# ioboard.net
KiCad netlist of a schematic drawn in EAGLE
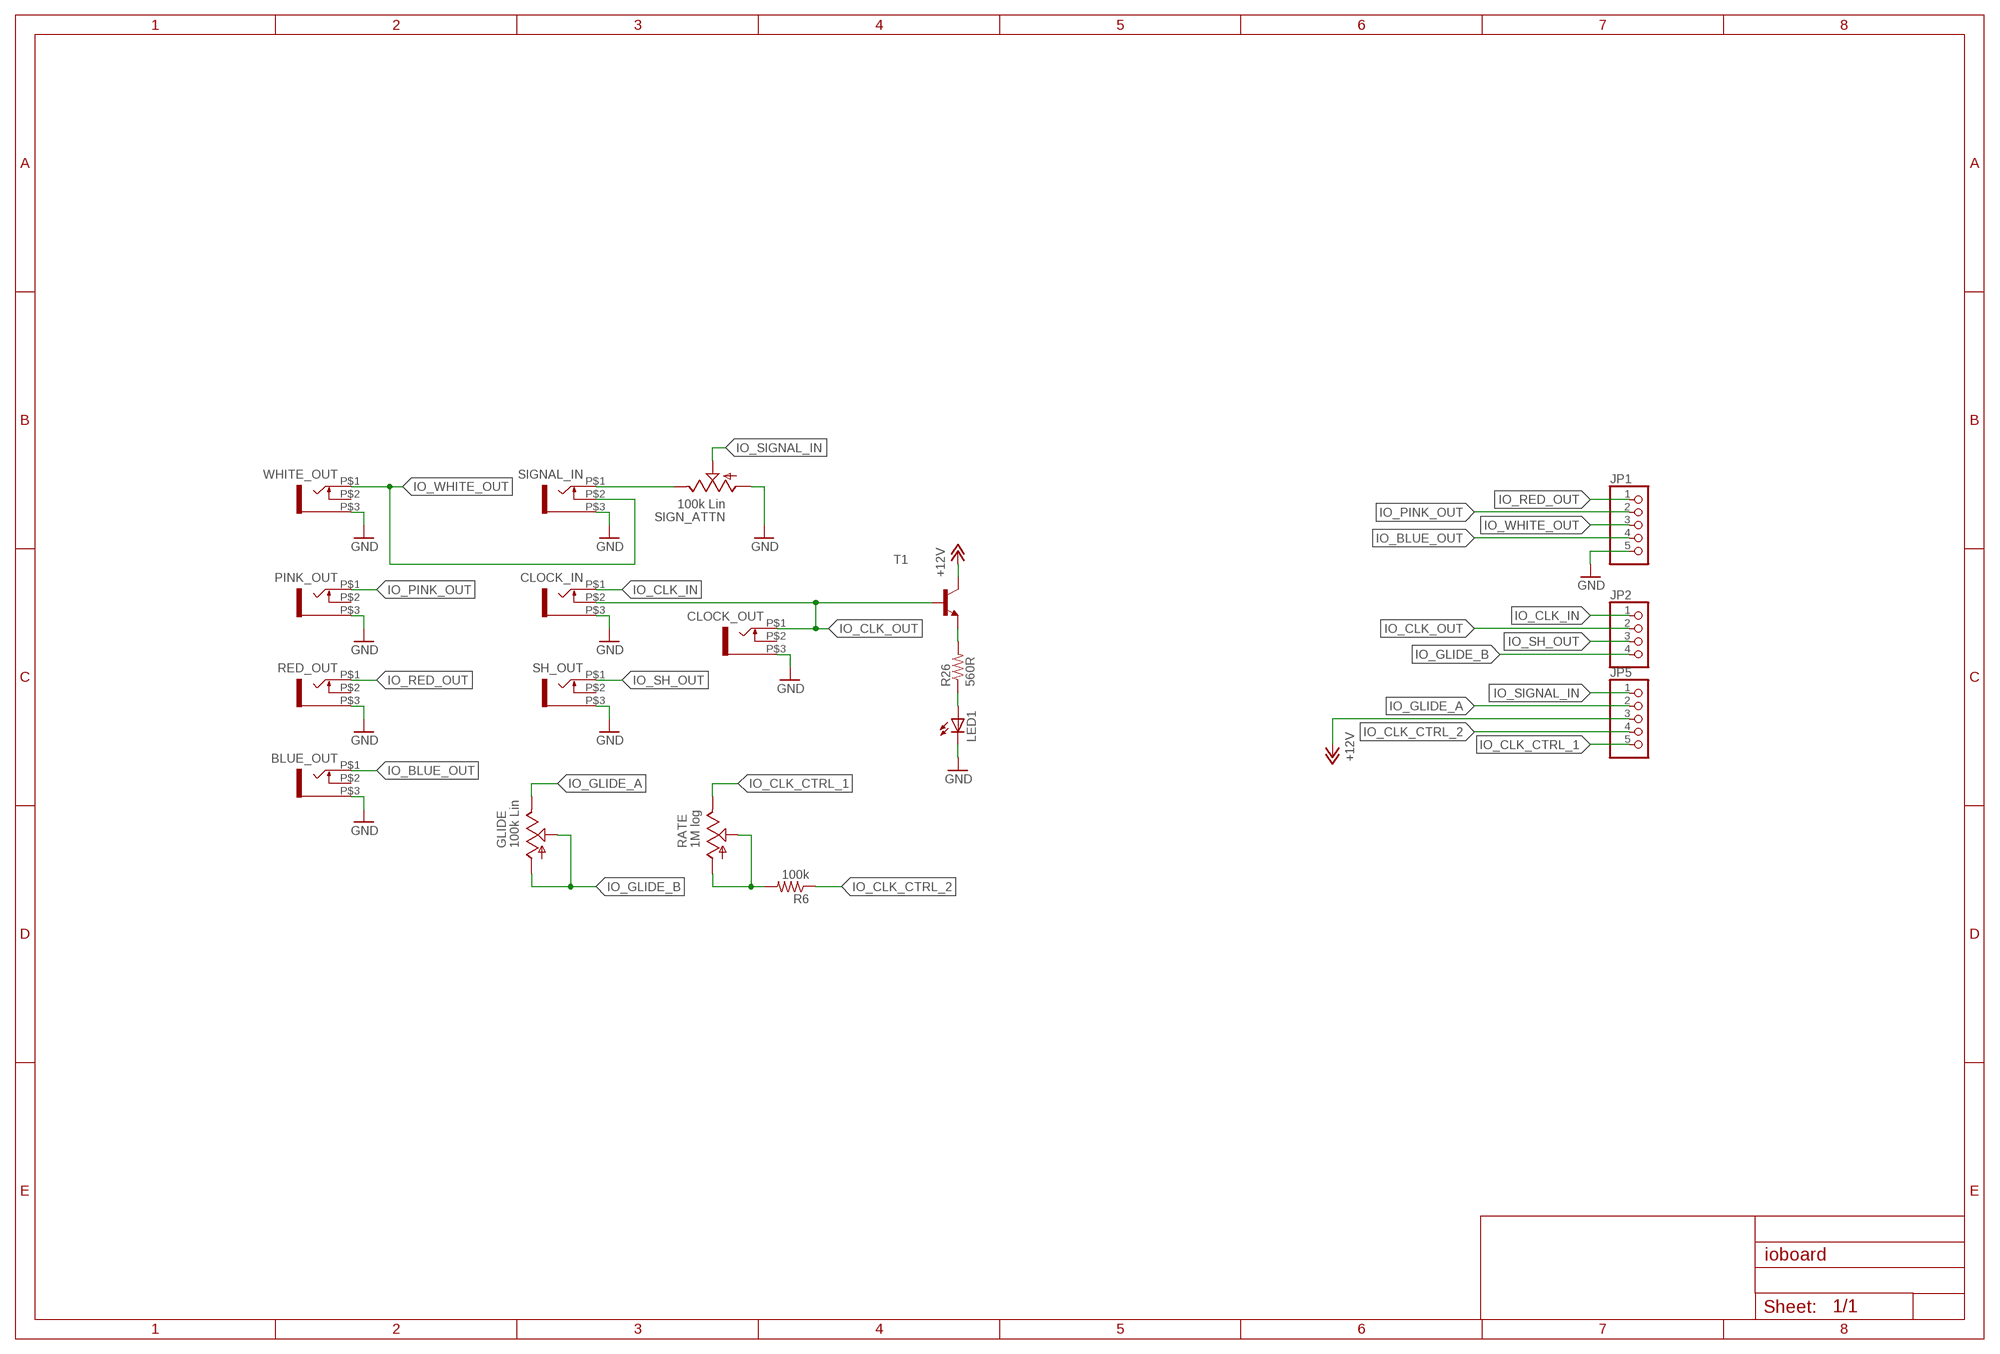
[diagram p0: schematic, sheet 1]

(export (version "E")
  (design (tool "Eeschema 10.0.6"))
  (components
    (comp (ref "BLUE_OUT")
      (value "WQP-PJ301M-12_JACK")
      (footprint "eagle-import:WQP-PJ301M-12_JACK")
      (libsource (lib "eagle-import") (part "WQP-PJ301M-12_JACK"))
    )
    (comp (ref "CLOCK_IN")
      (value "WQP-PJ301M-12_JACK")
      (footprint "eagle-import:WQP-PJ301M-12_JACK")
      (libsource (lib "eagle-import") (part "WQP-PJ301M-12_JACK"))
    )
    (comp (ref "CLOCK_OUT")
      (value "WQP-PJ301M-12_JACK")
      (footprint "eagle-import:WQP-PJ301M-12_JACK")
      (libsource (lib "eagle-import") (part "WQP-PJ301M-12_JACK"))
    )
    (comp (ref "GLIDE")
      (value "100k Lin")
      (footprint "eagle-import:EVUF")
      (libsource (lib "eagle-import") (part "ALPHA-9MMA"))
    )
    (comp (ref "JP1")
      (value "PINHD-1X5")
      (footprint "eagle-import:1X05")
      (libsource (lib "eagle-import") (part "PINHD-1X5"))
    )
    (comp (ref "JP2")
      (value "PINHD-1X4")
      (footprint "eagle-import:1X04")
      (libsource (lib "eagle-import") (part "PINHD-1X4"))
    )
    (comp (ref "JP5")
      (value "PINHD-1X5")
      (footprint "eagle-import:1X05")
      (libsource (lib "eagle-import") (part "PINHD-1X5"))
    )
    (comp (ref "LED1")
      (value "LED3MM")
      (footprint "eagle-import:LED3MM")
      (libsource (lib "eagle-import") (part "LED3MM"))
    )
    (comp (ref "PINK_OUT")
      (value "WQP-PJ301M-12_JACK")
      (footprint "eagle-import:WQP-PJ301M-12_JACK")
      (libsource (lib "eagle-import") (part "WQP-PJ301M-12_JACK"))
    )
    (comp (ref "R6")
      (value "100k")
      (footprint "eagle-import:0204_7")
      (libsource (lib "eagle-import") (part "R-US_0204/7"))
    )
    (comp (ref "R26")
      (value "560R")
      (footprint "eagle-import:0204_7")
      (libsource (lib "eagle-import") (part "R-US_0204/7"))
    )
    (comp (ref "RATE")
      (value "1M log")
      (footprint "eagle-import:EVUF")
      (libsource (lib "eagle-import") (part "ALPHA-9MMA"))
    )
    (comp (ref "RED_OUT")
      (value "WQP-PJ301M-12_JACK")
      (footprint "eagle-import:WQP-PJ301M-12_JACK")
      (libsource (lib "eagle-import") (part "WQP-PJ301M-12_JACK"))
    )
    (comp (ref "SH_OUT")
      (value "WQP-PJ301M-12_JACK")
      (footprint "eagle-import:WQP-PJ301M-12_JACK")
      (libsource (lib "eagle-import") (part "WQP-PJ301M-12_JACK"))
    )
    (comp (ref "SIGNAL_IN")
      (value "WQP-PJ301M-12_JACK")
      (footprint "eagle-import:WQP-PJ301M-12_JACK")
      (libsource (lib "eagle-import") (part "WQP-PJ301M-12_JACK"))
    )
    (comp (ref "SIGN_ATTN")
      (value "100k Lin")
      (footprint "eagle-import:EVUF")
      (libsource (lib "eagle-import") (part "ALPHA-9MMA"))
    )
    (comp (ref "T1")
      (value "BC550-NPN-TO92-CBE")
      (footprint "eagle-import:TO92-CBE")
      (libsource (lib "eagle-import") (part "-NPN-TO92-CBEBC550"))
    )
    (comp (ref "WHITE_OUT")
      (value "WQP-PJ301M-12_JACK")
      (footprint "eagle-import:WQP-PJ301M-12_JACK")
      (libsource (lib "eagle-import") (part "WQP-PJ301M-12_JACK"))
    )
  )
  (nets
    (net (code "1") (name "+12V") (class "Default")
      (node (ref "JP5") (pin "3") (pinfunction "3_3") (pintype "passive"))
      (node (ref "T1") (pin "C") (pinfunction "C_C") (pintype "passive"))
    )
    (net (code "2") (name "GND") (class "Default")
      (node (ref "BLUE_OUT") (pin "P$3") (pinfunction "1_P$3") (pintype "passive"))
      (node (ref "CLOCK_IN") (pin "P$3") (pinfunction "1_P$3") (pintype "passive"))
      (node (ref "CLOCK_OUT") (pin "P$3") (pinfunction "1_P$3") (pintype "passive"))
      (node (ref "JP1") (pin "5") (pinfunction "5_5") (pintype "passive"))
      (node (ref "LED1") (pin "K") (pinfunction "C_K") (pintype "passive"))
      (node (ref "PINK_OUT") (pin "P$3") (pinfunction "1_P$3") (pintype "passive"))
      (node (ref "RED_OUT") (pin "P$3") (pinfunction "1_P$3") (pintype "passive"))
      (node (ref "SH_OUT") (pin "P$3") (pinfunction "1_P$3") (pintype "passive"))
      (node (ref "SIGNAL_IN") (pin "P$3") (pinfunction "1_P$3") (pintype "passive"))
      (node (ref "SIGN_ATTN") (pin "1") (pinfunction "A_1") (pintype "passive"))
      (node (ref "WHITE_OUT") (pin "P$3") (pinfunction "1_P$3") (pintype "passive"))
    )
    (net (code "3") (name "IO_BLUE_OUT") (class "Default")
      (node (ref "BLUE_OUT") (pin "P$1") (pinfunction "2_P$1") (pintype "passive"))
      (node (ref "JP1") (pin "4") (pinfunction "4_4") (pintype "passive"))
    )
    (net (code "4") (name "IO_CLK_CTRL_1") (class "Default")
      (node (ref "JP5") (pin "5") (pinfunction "5_5") (pintype "passive"))
      (node (ref "RATE") (pin "3") (pinfunction "E_3") (pintype "passive"))
    )
    (net (code "5") (name "IO_CLK_CTRL_2") (class "Default")
      (node (ref "JP5") (pin "4") (pinfunction "4_4") (pintype "passive"))
      (node (ref "R6") (pin "1") (pinfunction "1_1") (pintype "passive"))
    )
    (net (code "6") (name "IO_CLK_IN") (class "Default")
      (node (ref "CLOCK_IN") (pin "P$1") (pinfunction "2_P$1") (pintype "passive"))
      (node (ref "JP2") (pin "1") (pinfunction "1_1") (pintype "passive"))
    )
    (net (code "7") (name "IO_CLK_OUT") (class "Default")
      (node (ref "CLOCK_IN") (pin "P$2") (pinfunction "3_P$2") (pintype "passive"))
      (node (ref "CLOCK_OUT") (pin "P$1") (pinfunction "2_P$1") (pintype "passive"))
      (node (ref "JP2") (pin "2") (pinfunction "2_2") (pintype "passive"))
      (node (ref "T1") (pin "B") (pinfunction "B_B") (pintype "passive"))
    )
    (net (code "8") (name "IO_GLIDE_A") (class "Default")
      (node (ref "GLIDE") (pin "3") (pinfunction "E_3") (pintype "passive"))
      (node (ref "JP5") (pin "2") (pinfunction "2_2") (pintype "passive"))
    )
    (net (code "9") (name "IO_GLIDE_B") (class "Default")
      (node (ref "GLIDE") (pin "1") (pinfunction "A_1") (pintype "passive"))
      (node (ref "GLIDE") (pin "2") (pinfunction "S_2") (pintype "passive"))
      (node (ref "JP2") (pin "4") (pinfunction "4_4") (pintype "passive"))
    )
    (net (code "10") (name "IO_PINK_OUT") (class "Default")
      (node (ref "JP1") (pin "2") (pinfunction "2_2") (pintype "passive"))
      (node (ref "PINK_OUT") (pin "P$1") (pinfunction "2_P$1") (pintype "passive"))
    )
    (net (code "11") (name "IO_RED_OUT") (class "Default")
      (node (ref "JP1") (pin "1") (pinfunction "1_1") (pintype "passive"))
      (node (ref "RED_OUT") (pin "P$1") (pinfunction "2_P$1") (pintype "passive"))
    )
    (net (code "12") (name "IO_SH_OUT") (class "Default")
      (node (ref "JP2") (pin "3") (pinfunction "3_3") (pintype "passive"))
      (node (ref "SH_OUT") (pin "P$1") (pinfunction "2_P$1") (pintype "passive"))
    )
    (net (code "13") (name "IO_SIGNAL_IN") (class "Default")
      (node (ref "JP5") (pin "1") (pinfunction "1_1") (pintype "passive"))
      (node (ref "SIGN_ATTN") (pin "2") (pinfunction "S_2") (pintype "passive"))
    )
    (net (code "14") (name "IO_WHITE_OUT") (class "Default")
      (node (ref "JP1") (pin "3") (pinfunction "3_3") (pintype "passive"))
      (node (ref "SIGNAL_IN") (pin "P$2") (pinfunction "3_P$2") (pintype "passive"))
      (node (ref "WHITE_OUT") (pin "P$1") (pinfunction "2_P$1") (pintype "passive"))
    )
    (net (code "15") (name "Net-(LED1-PadA)") (class "Default")
      (node (ref "LED1") (pin "A") (pinfunction "A_A") (pintype "passive"))
      (node (ref "R26") (pin "1") (pinfunction "1_1") (pintype "passive"))
    )
    (net (code "16") (name "Net-(R26-Pad2)") (class "Default")
      (node (ref "R26") (pin "2") (pinfunction "2_2") (pintype "passive"))
      (node (ref "T1") (pin "E") (pinfunction "E_E") (pintype "passive"))
    )
    (net (code "17") (name "Net-(RATE-A)") (class "Default")
      (node (ref "R6") (pin "2") (pinfunction "2_2") (pintype "passive"))
      (node (ref "RATE") (pin "1") (pinfunction "A_1") (pintype "passive"))
      (node (ref "RATE") (pin "2") (pinfunction "S_2") (pintype "passive"))
    )
    (net (code "18") (name "Net-(SIGNAL_IN-2)") (class "Default")
      (node (ref "SIGNAL_IN") (pin "P$1") (pinfunction "2_P$1") (pintype "passive"))
      (node (ref "SIGN_ATTN") (pin "3") (pinfunction "E_3") (pintype "passive"))
    )
    (net (code "19") (name "unconnected-(BLUE_OUT-3-PadP$2)") (class "Default")
      (node (ref "BLUE_OUT") (pin "P$2") (pinfunction "3_P$2") (pintype "passive"))
    )
    (net (code "20") (name "unconnected-(CLOCK_OUT-3-PadP$2)") (class "Default")
      (node (ref "CLOCK_OUT") (pin "P$2") (pinfunction "3_P$2") (pintype "passive"))
    )
    (net (code "21") (name "unconnected-(PINK_OUT-3-PadP$2)") (class "Default")
      (node (ref "PINK_OUT") (pin "P$2") (pinfunction "3_P$2") (pintype "passive"))
    )
    (net (code "22") (name "unconnected-(RED_OUT-3-PadP$2)") (class "Default")
      (node (ref "RED_OUT") (pin "P$2") (pinfunction "3_P$2") (pintype "passive"))
    )
    (net (code "23") (name "unconnected-(SH_OUT-3-PadP$2)") (class "Default")
      (node (ref "SH_OUT") (pin "P$2") (pinfunction "3_P$2") (pintype "passive"))
    )
    (net (code "24") (name "unconnected-(WHITE_OUT-3-PadP$2)") (class "Default")
      (node (ref "WHITE_OUT") (pin "P$2") (pinfunction "3_P$2") (pintype "passive"))
    )
  )
)
